# ProProject_Orin_Adapter_2025-03-09.net
KiCad netlist of a schematic drawn in EasyEDA Pro
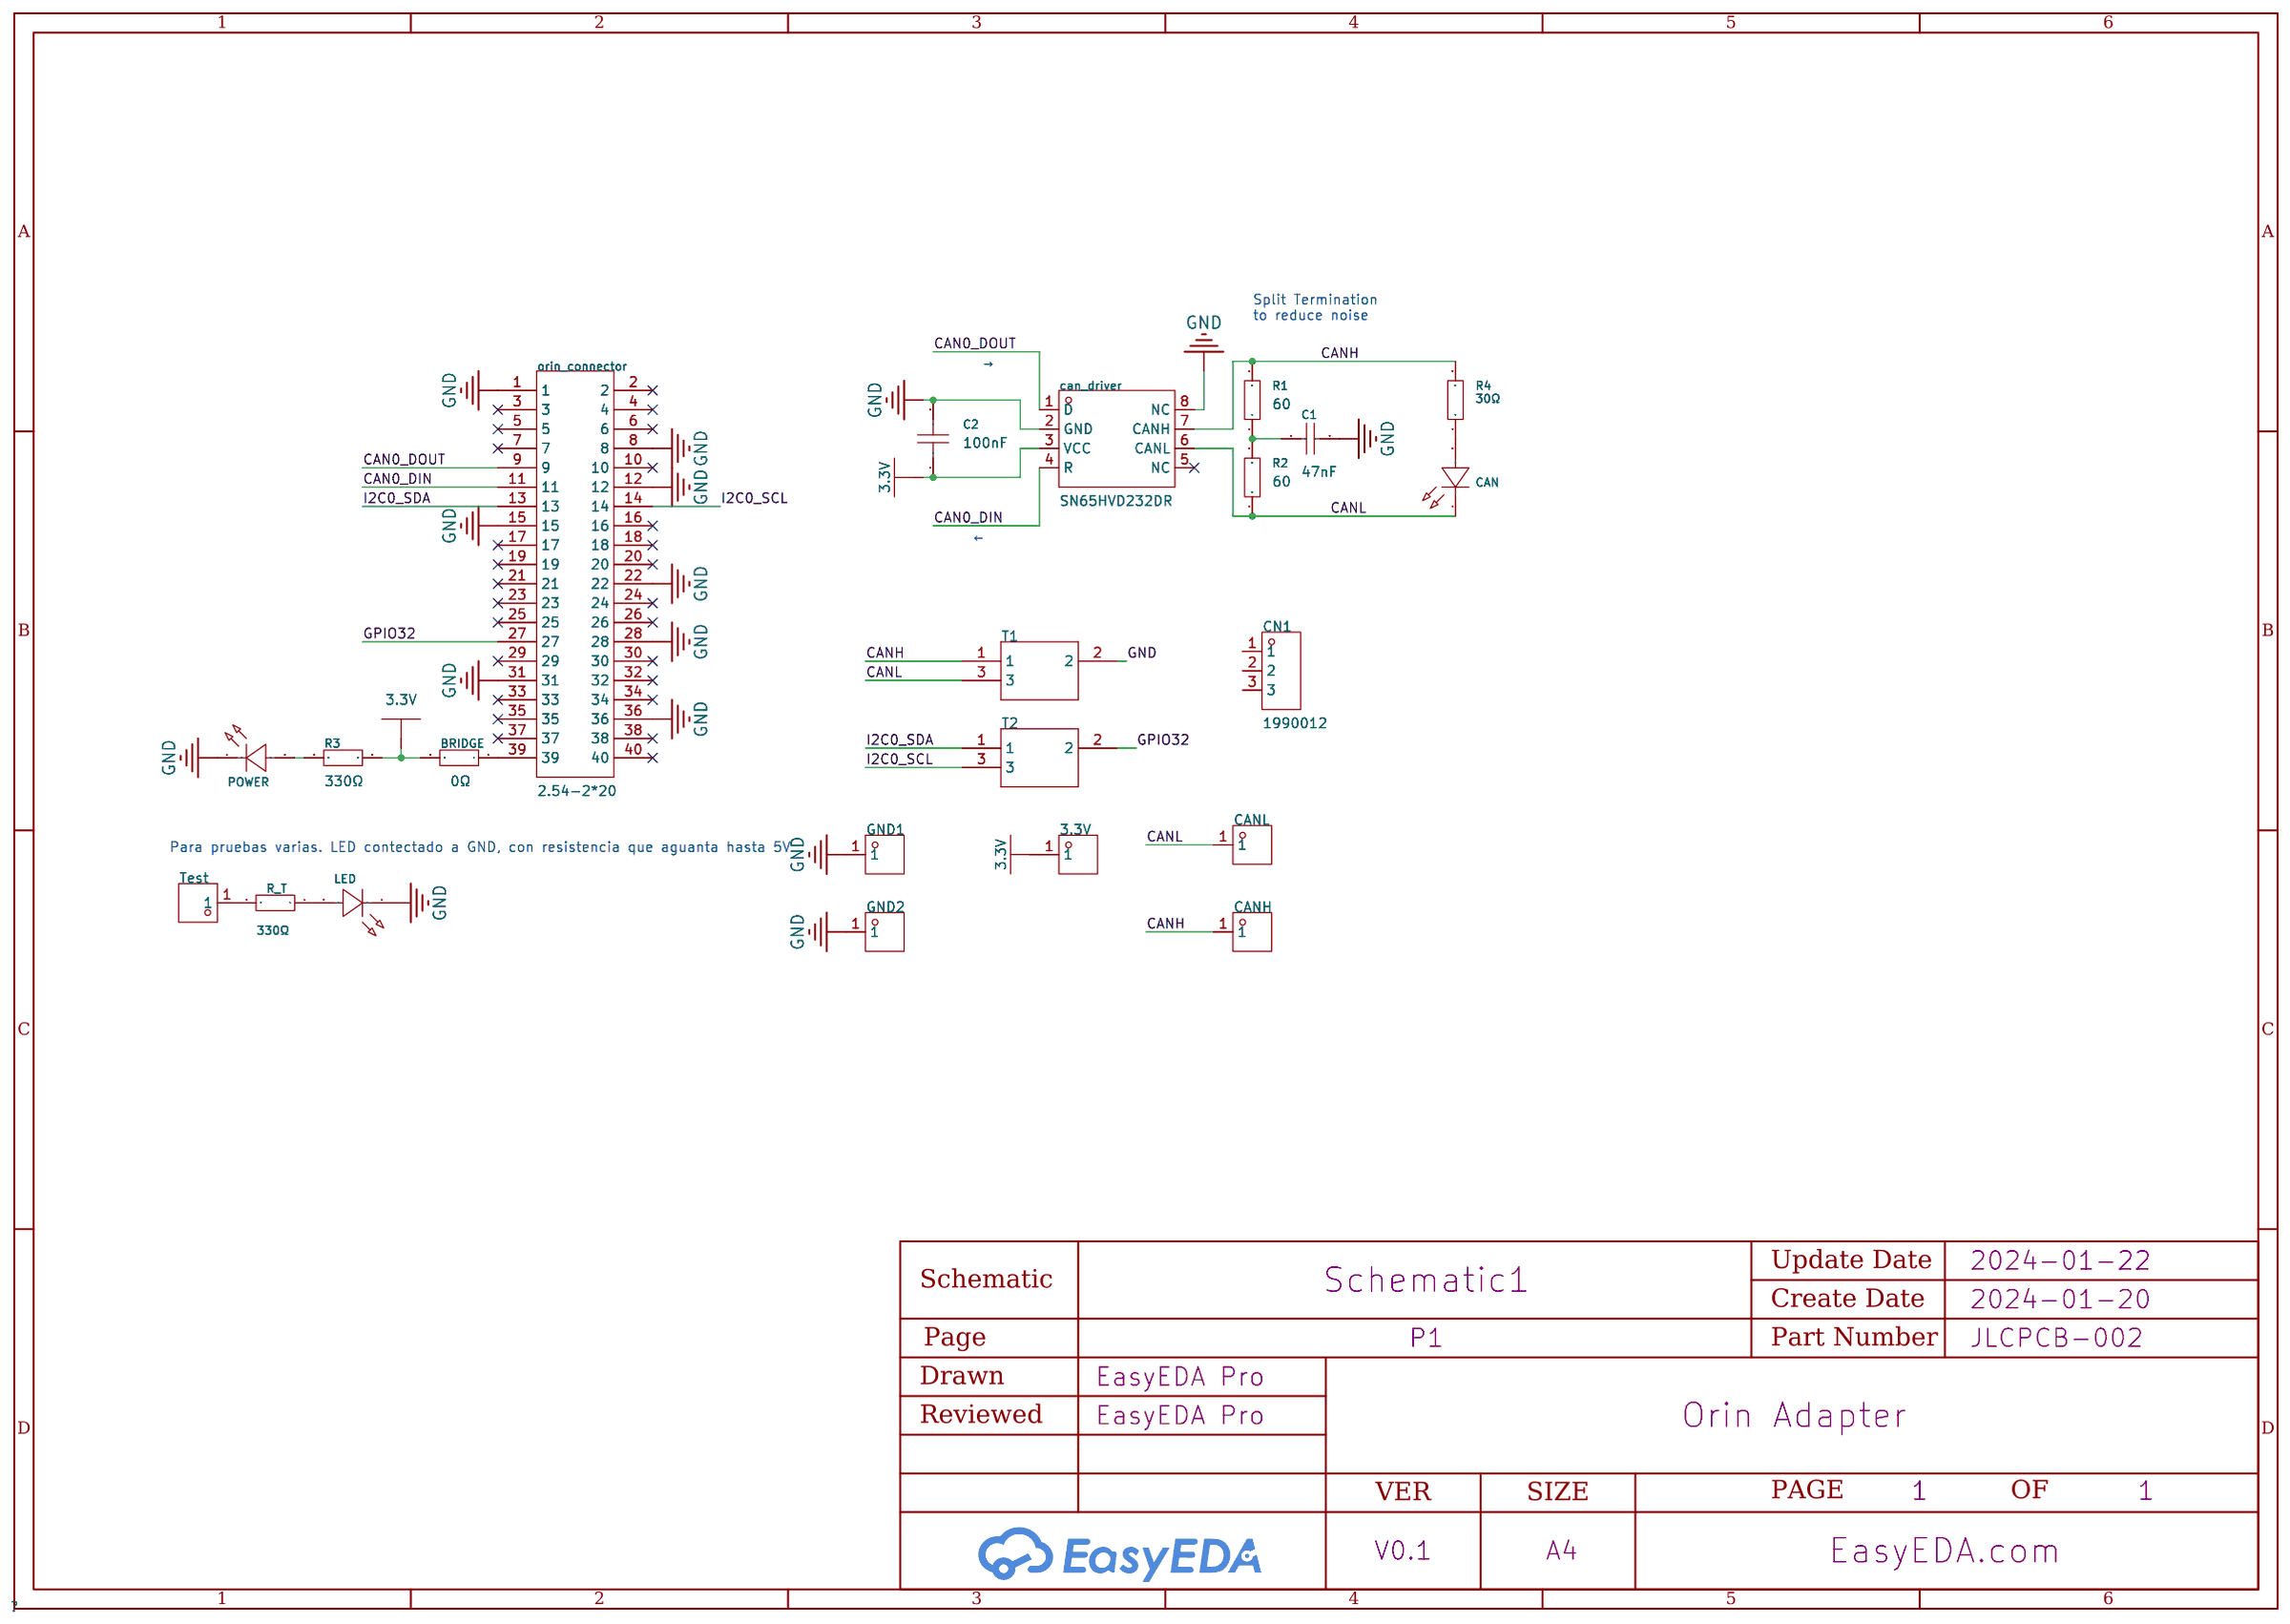
[diagram p0: schematic sheet]

(export (version "E")
  (design (tool "Eeschema 10.0.6"))
  (components
    (comp (ref "3.3V")
      (value "5-146868-1")
      (footprint "easyedapro:HDR-TH_1P-P2.54-V-M_1")
      (fields (field (name "Manufacturer") "TE Connectivity(泰科电子)"))
      (libsource (lib "easyedapro") (part "5-146868-1"))
    )
    (comp (ref "BRIDGE")
      (value "0Ω")
      (footprint "easyedapro:R0603")
      (fields
        (field (name "Manufacturer Part") "0603WAF0000T5E")
        (field (name "Manufacturer") "UNI-ROYAL(厚声)")
      )
      (libsource (lib "easyedapro") (part "0603WAF0000T5E"))
    )
    (comp (ref "C1")
      (value "47nF")
      (footprint "easyedapro:C0603")
      (fields
        (field (name "Manufacturer Part") "CC0603KRX7R9BB473")
        (field (name "Manufacturer") "YAGEO(国巨)")
      )
      (libsource (lib "easyedapro") (part "CC0603KRX7R9BB473"))
    )
    (comp (ref "C2")
      (value "100nF")
      (footprint "easyedapro:C0603")
      (fields
        (field (name "Manufacturer Part") "CC0603MRY5V8BB104")
        (field (name "Manufacturer") "YAGEO(国巨)")
      )
      (libsource (lib "easyedapro") (part "CC0603MRY5V8BB104"))
    )
    (comp (ref "CAN")
      (value "150060GS75000")
      (footprint "easyedapro:LED0603-RD_GREEN")
      (fields (field (name "Manufacturer") "Wurth(伍尔特)"))
      (libsource (lib "easyedapro") (part "150060GS75000"))
    )
    (comp (ref "CANH")
      (value "5-146868-1")
      (footprint "easyedapro:HDR-TH_1P-P2.54-V-M_1")
      (fields (field (name "Manufacturer") "TE Connectivity(泰科电子)"))
      (libsource (lib "easyedapro") (part "5-146868-1"))
    )
    (comp (ref "CANL")
      (value "5-146868-1")
      (footprint "easyedapro:HDR-TH_1P-P2.54-V-M_1")
      (fields (field (name "Manufacturer") "TE Connectivity(泰科电子)"))
      (libsource (lib "easyedapro") (part "5-146868-1"))
    )
    (comp (ref "can_driver")
      (value "SN65HVD232DR")
      (footprint "easyedapro:SOIC-8_L5.0-W4.0-P1.27-LS6.0-BL")
      (description "Type:Transceiver Data Rate:1Mbps Supply Voltage:3V~3.6V Supply Voltage:3V~3.6V")
      (fields (field (name "Manufacturer") "TI(德州仪器)"))
      (libsource (lib "easyedapro") (part "SN65HVD232DR"))
    )
    (comp (ref "CN1")
      (value "1990012")
      (footprint "easyedapro:CONN-TH_3P-P2.50-S5.00_1990012")
      (libsource (lib "easyedapro") (part "1990012"))
    )
    (comp (ref "GND1")
      (value "5-146868-1")
      (footprint "easyedapro:HDR-TH_1P-P2.54-V-M_1")
      (fields (field (name "Manufacturer") "TE Connectivity(泰科电子)"))
      (libsource (lib "easyedapro") (part "5-146868-1"))
    )
    (comp (ref "GND2")
      (value "5-146868-1")
      (footprint "easyedapro:HDR-TH_1P-P2.54-V-M_1")
      (fields (field (name "Manufacturer") "TE Connectivity(泰科电子)"))
      (libsource (lib "easyedapro") (part "5-146868-1"))
    )
    (comp (ref "LED")
      (value "150060GS75000")
      (footprint "easyedapro:LED0603-RD_GREEN")
      (fields (field (name "Manufacturer") "Wurth(伍尔特)"))
      (libsource (lib "easyedapro") (part "150060GS75000"))
    )
    (comp (ref "orin_connector")
      (value "2.54-2*20")
      (footprint "easyedapro:HDR-TH_40P-P2.54-V-F-R2-C20-S2.54")
      (fields (field (name "Manufacturer") "ZHOURI(洲日)"))
      (libsource (lib "easyedapro") (part "2.54-2*20"))
    )
    (comp (ref "POWER")
      (value "150060GS75000")
      (footprint "easyedapro:LED0603-RD_GREEN")
      (fields (field (name "Manufacturer") "Wurth(伍尔特)"))
      (libsource (lib "easyedapro") (part "150060GS75000"))
    )
    (comp (ref "R1")
      (value "60")
      (footprint "easyedapro:R0603")
      (fields
        (field (name "Manufacturer Part") "0603WAF1002T5E")
        (field (name "Manufacturer") "UNI-ROYAL(厚声)")
      )
      (libsource (lib "easyedapro") (part "0603WAF1002T5E"))
    )
    (comp (ref "R2")
      (value "60")
      (footprint "easyedapro:R0603")
      (fields
        (field (name "Manufacturer Part") "0603WAF1002T5E")
        (field (name "Manufacturer") "UNI-ROYAL(厚声)")
      )
      (libsource (lib "easyedapro") (part "0603WAF1002T5E"))
    )
    (comp (ref "R3")
      (value "330Ω")
      (footprint "easyedapro:R0603")
      (fields
        (field (name "Manufacturer Part") "0603WAF3300T5E")
        (field (name "Manufacturer") "UNI-ROYAL(厚声)")
      )
      (libsource (lib "easyedapro") (part "0603WAF3300T5E"))
    )
    (comp (ref "R4")
      (value "30Ω")
      (footprint "easyedapro:R0603")
      (fields
        (field (name "Manufacturer Part") "0603WAF3300T5E")
        (field (name "Manufacturer") "UNI-ROYAL(厚声)")
      )
      (libsource (lib "easyedapro") (part "0603WAF3300T5E"))
    )
    (comp (ref "R_T")
      (value "330Ω")
      (footprint "easyedapro:R0603")
      (fields
        (field (name "Manufacturer Part") "0603WAF3300T5E")
        (field (name "Manufacturer") "UNI-ROYAL(厚声)")
      )
      (libsource (lib "easyedapro") (part "0603WAF3300T5E"))
    )
    (comp (ref "T1")
      (value "~")
      (footprint "easyedapro:1990012")
      (libsource (lib "easyedapro") (part "1990012_"))
    )
    (comp (ref "T2")
      (value "~")
      (footprint "easyedapro:1990012")
      (libsource (lib "easyedapro") (part "1990012_"))
    )
    (comp (ref "Test")
      (value "5-146868-1")
      (footprint "easyedapro:HDR-TH_1P-P2.54-V-M_1")
      (fields (field (name "Manufacturer") "TE Connectivity(泰科电子)"))
      (libsource (lib "easyedapro") (part "5-146868-1"))
    )
  )
  (nets
    (net (code "1") (name "/CAN0_DIN") (class "Default")
      (node (ref "can_driver") (pin "4") (pinfunction "R_4") (pintype "input"))
      (node (ref "orin_connector") (pin "11") (pinfunction "11_11") (pintype "input"))
    )
    (net (code "2") (name "/CAN0_DOUT") (class "Default")
      (node (ref "can_driver") (pin "1") (pinfunction "D_1") (pintype "input"))
      (node (ref "orin_connector") (pin "9") (pinfunction "9_9") (pintype "input"))
    )
    (net (code "3") (name "/CANH") (class "Default")
      (node (ref "CANH") (pin "1") (pinfunction "1_1") (pintype "unspecified"))
      (node (ref "R1") (pin "2") (pinfunction "2_2") (pintype "input"))
      (node (ref "R4") (pin "2") (pinfunction "2_2") (pintype "input"))
      (node (ref "T1") (pin "1") (pinfunction "1_1") (pintype "bidirectional"))
      (node (ref "can_driver") (pin "7") (pinfunction "CANH_7") (pintype "input"))
    )
    (net (code "4") (name "/CANL") (class "Default")
      (node (ref "CAN") (pin "1") (pinfunction "K_1") (pintype "input"))
      (node (ref "CANL") (pin "1") (pinfunction "1_1") (pintype "unspecified"))
      (node (ref "R2") (pin "1") (pinfunction "1_1") (pintype "input"))
      (node (ref "T1") (pin "3") (pinfunction "3_3") (pintype "bidirectional"))
      (node (ref "can_driver") (pin "6") (pinfunction "CANL_6") (pintype "input"))
    )
    (net (code "5") (name "/GPIO32") (class "Default")
      (node (ref "T2") (pin "2") (pinfunction "2_2") (pintype "bidirectional"))
      (node (ref "orin_connector") (pin "27") (pinfunction "27_27") (pintype "input"))
    )
    (net (code "6") (name "/I2C0_SCL") (class "Default")
      (node (ref "T2") (pin "3") (pinfunction "3_3") (pintype "bidirectional"))
      (node (ref "orin_connector") (pin "14") (pinfunction "14_14") (pintype "input"))
    )
    (net (code "7") (name "/I2C0_SDA") (class "Default")
      (node (ref "T2") (pin "1") (pinfunction "1_1") (pintype "bidirectional"))
      (node (ref "orin_connector") (pin "13") (pinfunction "13_13") (pintype "input"))
    )
    (net (code "8") (name "3.3V") (class "Default")
      (node (ref "3.3V") (pin "1") (pinfunction "1_1") (pintype "unspecified"))
      (node (ref "BRIDGE") (pin "2") (pinfunction "2_2") (pintype "input"))
      (node (ref "C2") (pin "1") (pinfunction "1_1") (pintype "input"))
      (node (ref "R3") (pin "2") (pinfunction "2_2") (pintype "input"))
      (node (ref "can_driver") (pin "3") (pinfunction "VCC_3") (pintype "input"))
    )
    (net (code "9") (name "GND") (class "Default")
      (node (ref "C1") (pin "2") (pinfunction "2_2") (pintype "input"))
      (node (ref "C2") (pin "2") (pinfunction "2_2") (pintype "input"))
      (node (ref "GND1") (pin "1") (pinfunction "1_1") (pintype "unspecified"))
      (node (ref "GND2") (pin "1") (pinfunction "1_1") (pintype "unspecified"))
      (node (ref "LED") (pin "1") (pinfunction "K_1") (pintype "input"))
      (node (ref "POWER") (pin "1") (pinfunction "K_1") (pintype "input"))
      (node (ref "T1") (pin "2") (pinfunction "2_2") (pintype "bidirectional"))
      (node (ref "can_driver") (pin "2") (pinfunction "GND_2") (pintype "input"))
      (node (ref "can_driver") (pin "8") (pinfunction "NC_8") (pintype "input"))
      (node (ref "orin_connector") (pin "1") (pinfunction "1_1") (pintype "input"))
      (node (ref "orin_connector") (pin "12") (pinfunction "12_12") (pintype "input"))
      (node (ref "orin_connector") (pin "15") (pinfunction "15_15") (pintype "input"))
      (node (ref "orin_connector") (pin "22") (pinfunction "22_22") (pintype "input"))
      (node (ref "orin_connector") (pin "28") (pinfunction "28_28") (pintype "input"))
      (node (ref "orin_connector") (pin "31") (pinfunction "31_31") (pintype "input"))
      (node (ref "orin_connector") (pin "36") (pinfunction "36_36") (pintype "input"))
      (node (ref "orin_connector") (pin "8") (pinfunction "8_8") (pintype "input"))
    )
    (net (code "10") (name "Net-(BRIDGE-Pad1)") (class "Default")
      (node (ref "BRIDGE") (pin "1") (pinfunction "1_1") (pintype "input"))
      (node (ref "orin_connector") (pin "39") (pinfunction "39_39") (pintype "input"))
    )
    (net (code "11") (name "Net-(C1-Pad1)") (class "Default")
      (node (ref "C1") (pin "1") (pinfunction "1_1") (pintype "input"))
      (node (ref "R1") (pin "1") (pinfunction "1_1") (pintype "input"))
      (node (ref "R2") (pin "2") (pinfunction "2_2") (pintype "input"))
    )
    (net (code "12") (name "Net-(CAN-A)") (class "Default")
      (node (ref "CAN") (pin "2") (pinfunction "A_2") (pintype "input"))
      (node (ref "R4") (pin "1") (pinfunction "1_1") (pintype "input"))
    )
    (net (code "13") (name "Net-(LED-A)") (class "Default")
      (node (ref "LED") (pin "2") (pinfunction "A_2") (pintype "input"))
      (node (ref "R_T") (pin "1") (pinfunction "1_1") (pintype "input"))
    )
    (net (code "14") (name "Net-(POWER-A)") (class "Default")
      (node (ref "POWER") (pin "2") (pinfunction "A_2") (pintype "input"))
      (node (ref "R3") (pin "1") (pinfunction "1_1") (pintype "input"))
    )
    (net (code "15") (name "Net-(R_T-Pad2)") (class "Default")
      (node (ref "R_T") (pin "2") (pinfunction "2_2") (pintype "input"))
      (node (ref "Test") (pin "1") (pinfunction "1_1") (pintype "unspecified"))
    )
    (net (code "16") (name "unconnected-(CN1-Pad1)") (class "Default")
      (node (ref "CN1") (pin "1") (pinfunction "1_1") (pintype "unspecified"))
    )
    (net (code "17") (name "unconnected-(CN1-Pad2)") (class "Default")
      (node (ref "CN1") (pin "2") (pinfunction "2_2") (pintype "unspecified"))
    )
    (net (code "18") (name "unconnected-(CN1-Pad3)") (class "Default")
      (node (ref "CN1") (pin "3") (pinfunction "3_3") (pintype "unspecified"))
    )
    (net (code "19") (name "unconnected-(can_driver-NC-Pad5)") (class "Default")
      (node (ref "can_driver") (pin "5") (pinfunction "NC_5") (pintype "input+no_connect"))
    )
    (net (code "20") (name "unconnected-(orin_connector-Pad2)") (class "Default")
      (node (ref "orin_connector") (pin "2") (pinfunction "2_2") (pintype "input+no_connect"))
    )
    (net (code "21") (name "unconnected-(orin_connector-Pad3)") (class "Default")
      (node (ref "orin_connector") (pin "3") (pinfunction "3_3") (pintype "input+no_connect"))
    )
    (net (code "22") (name "unconnected-(orin_connector-Pad4)") (class "Default")
      (node (ref "orin_connector") (pin "4") (pinfunction "4_4") (pintype "input+no_connect"))
    )
    (net (code "23") (name "unconnected-(orin_connector-Pad5)") (class "Default")
      (node (ref "orin_connector") (pin "5") (pinfunction "5_5") (pintype "input+no_connect"))
    )
    (net (code "24") (name "unconnected-(orin_connector-Pad6)") (class "Default")
      (node (ref "orin_connector") (pin "6") (pinfunction "6_6") (pintype "input+no_connect"))
    )
    (net (code "25") (name "unconnected-(orin_connector-Pad7)") (class "Default")
      (node (ref "orin_connector") (pin "7") (pinfunction "7_7") (pintype "input+no_connect"))
    )
    (net (code "26") (name "unconnected-(orin_connector-Pad10)") (class "Default")
      (node (ref "orin_connector") (pin "10") (pinfunction "10_10") (pintype "input+no_connect"))
    )
    (net (code "27") (name "unconnected-(orin_connector-Pad16)") (class "Default")
      (node (ref "orin_connector") (pin "16") (pinfunction "16_16") (pintype "input+no_connect"))
    )
    (net (code "28") (name "unconnected-(orin_connector-Pad17)") (class "Default")
      (node (ref "orin_connector") (pin "17") (pinfunction "17_17") (pintype "input+no_connect"))
    )
    (net (code "29") (name "unconnected-(orin_connector-Pad18)") (class "Default")
      (node (ref "orin_connector") (pin "18") (pinfunction "18_18") (pintype "input+no_connect"))
    )
    (net (code "30") (name "unconnected-(orin_connector-Pad19)") (class "Default")
      (node (ref "orin_connector") (pin "19") (pinfunction "19_19") (pintype "input+no_connect"))
    )
    (net (code "31") (name "unconnected-(orin_connector-Pad20)") (class "Default")
      (node (ref "orin_connector") (pin "20") (pinfunction "20_20") (pintype "input+no_connect"))
    )
    (net (code "32") (name "unconnected-(orin_connector-Pad21)") (class "Default")
      (node (ref "orin_connector") (pin "21") (pinfunction "21_21") (pintype "input+no_connect"))
    )
    (net (code "33") (name "unconnected-(orin_connector-Pad23)") (class "Default")
      (node (ref "orin_connector") (pin "23") (pinfunction "23_23") (pintype "input+no_connect"))
    )
    (net (code "34") (name "unconnected-(orin_connector-Pad24)") (class "Default")
      (node (ref "orin_connector") (pin "24") (pinfunction "24_24") (pintype "input+no_connect"))
    )
    (net (code "35") (name "unconnected-(orin_connector-Pad25)") (class "Default")
      (node (ref "orin_connector") (pin "25") (pinfunction "25_25") (pintype "input+no_connect"))
    )
    (net (code "36") (name "unconnected-(orin_connector-Pad26)") (class "Default")
      (node (ref "orin_connector") (pin "26") (pinfunction "26_26") (pintype "input+no_connect"))
    )
    (net (code "37") (name "unconnected-(orin_connector-Pad29)") (class "Default")
      (node (ref "orin_connector") (pin "29") (pinfunction "29_29") (pintype "input+no_connect"))
    )
    (net (code "38") (name "unconnected-(orin_connector-Pad30)") (class "Default")
      (node (ref "orin_connector") (pin "30") (pinfunction "30_30") (pintype "input+no_connect"))
    )
    (net (code "39") (name "unconnected-(orin_connector-Pad32)") (class "Default")
      (node (ref "orin_connector") (pin "32") (pinfunction "32_32") (pintype "input+no_connect"))
    )
    (net (code "40") (name "unconnected-(orin_connector-Pad33)") (class "Default")
      (node (ref "orin_connector") (pin "33") (pinfunction "33_33") (pintype "input+no_connect"))
    )
    (net (code "41") (name "unconnected-(orin_connector-Pad34)") (class "Default")
      (node (ref "orin_connector") (pin "34") (pinfunction "34_34") (pintype "input+no_connect"))
    )
    (net (code "42") (name "unconnected-(orin_connector-Pad35)") (class "Default")
      (node (ref "orin_connector") (pin "35") (pinfunction "35_35") (pintype "input+no_connect"))
    )
    (net (code "43") (name "unconnected-(orin_connector-Pad37)") (class "Default")
      (node (ref "orin_connector") (pin "37") (pinfunction "37_37") (pintype "input+no_connect"))
    )
    (net (code "44") (name "unconnected-(orin_connector-Pad38)") (class "Default")
      (node (ref "orin_connector") (pin "38") (pinfunction "38_38") (pintype "input+no_connect"))
    )
    (net (code "45") (name "unconnected-(orin_connector-Pad40)") (class "Default")
      (node (ref "orin_connector") (pin "40") (pinfunction "40_40") (pintype "input+no_connect"))
    )
  )
)
